# SPI_IFC.net
KiCad netlist of a schematic drawn in Altium Designer
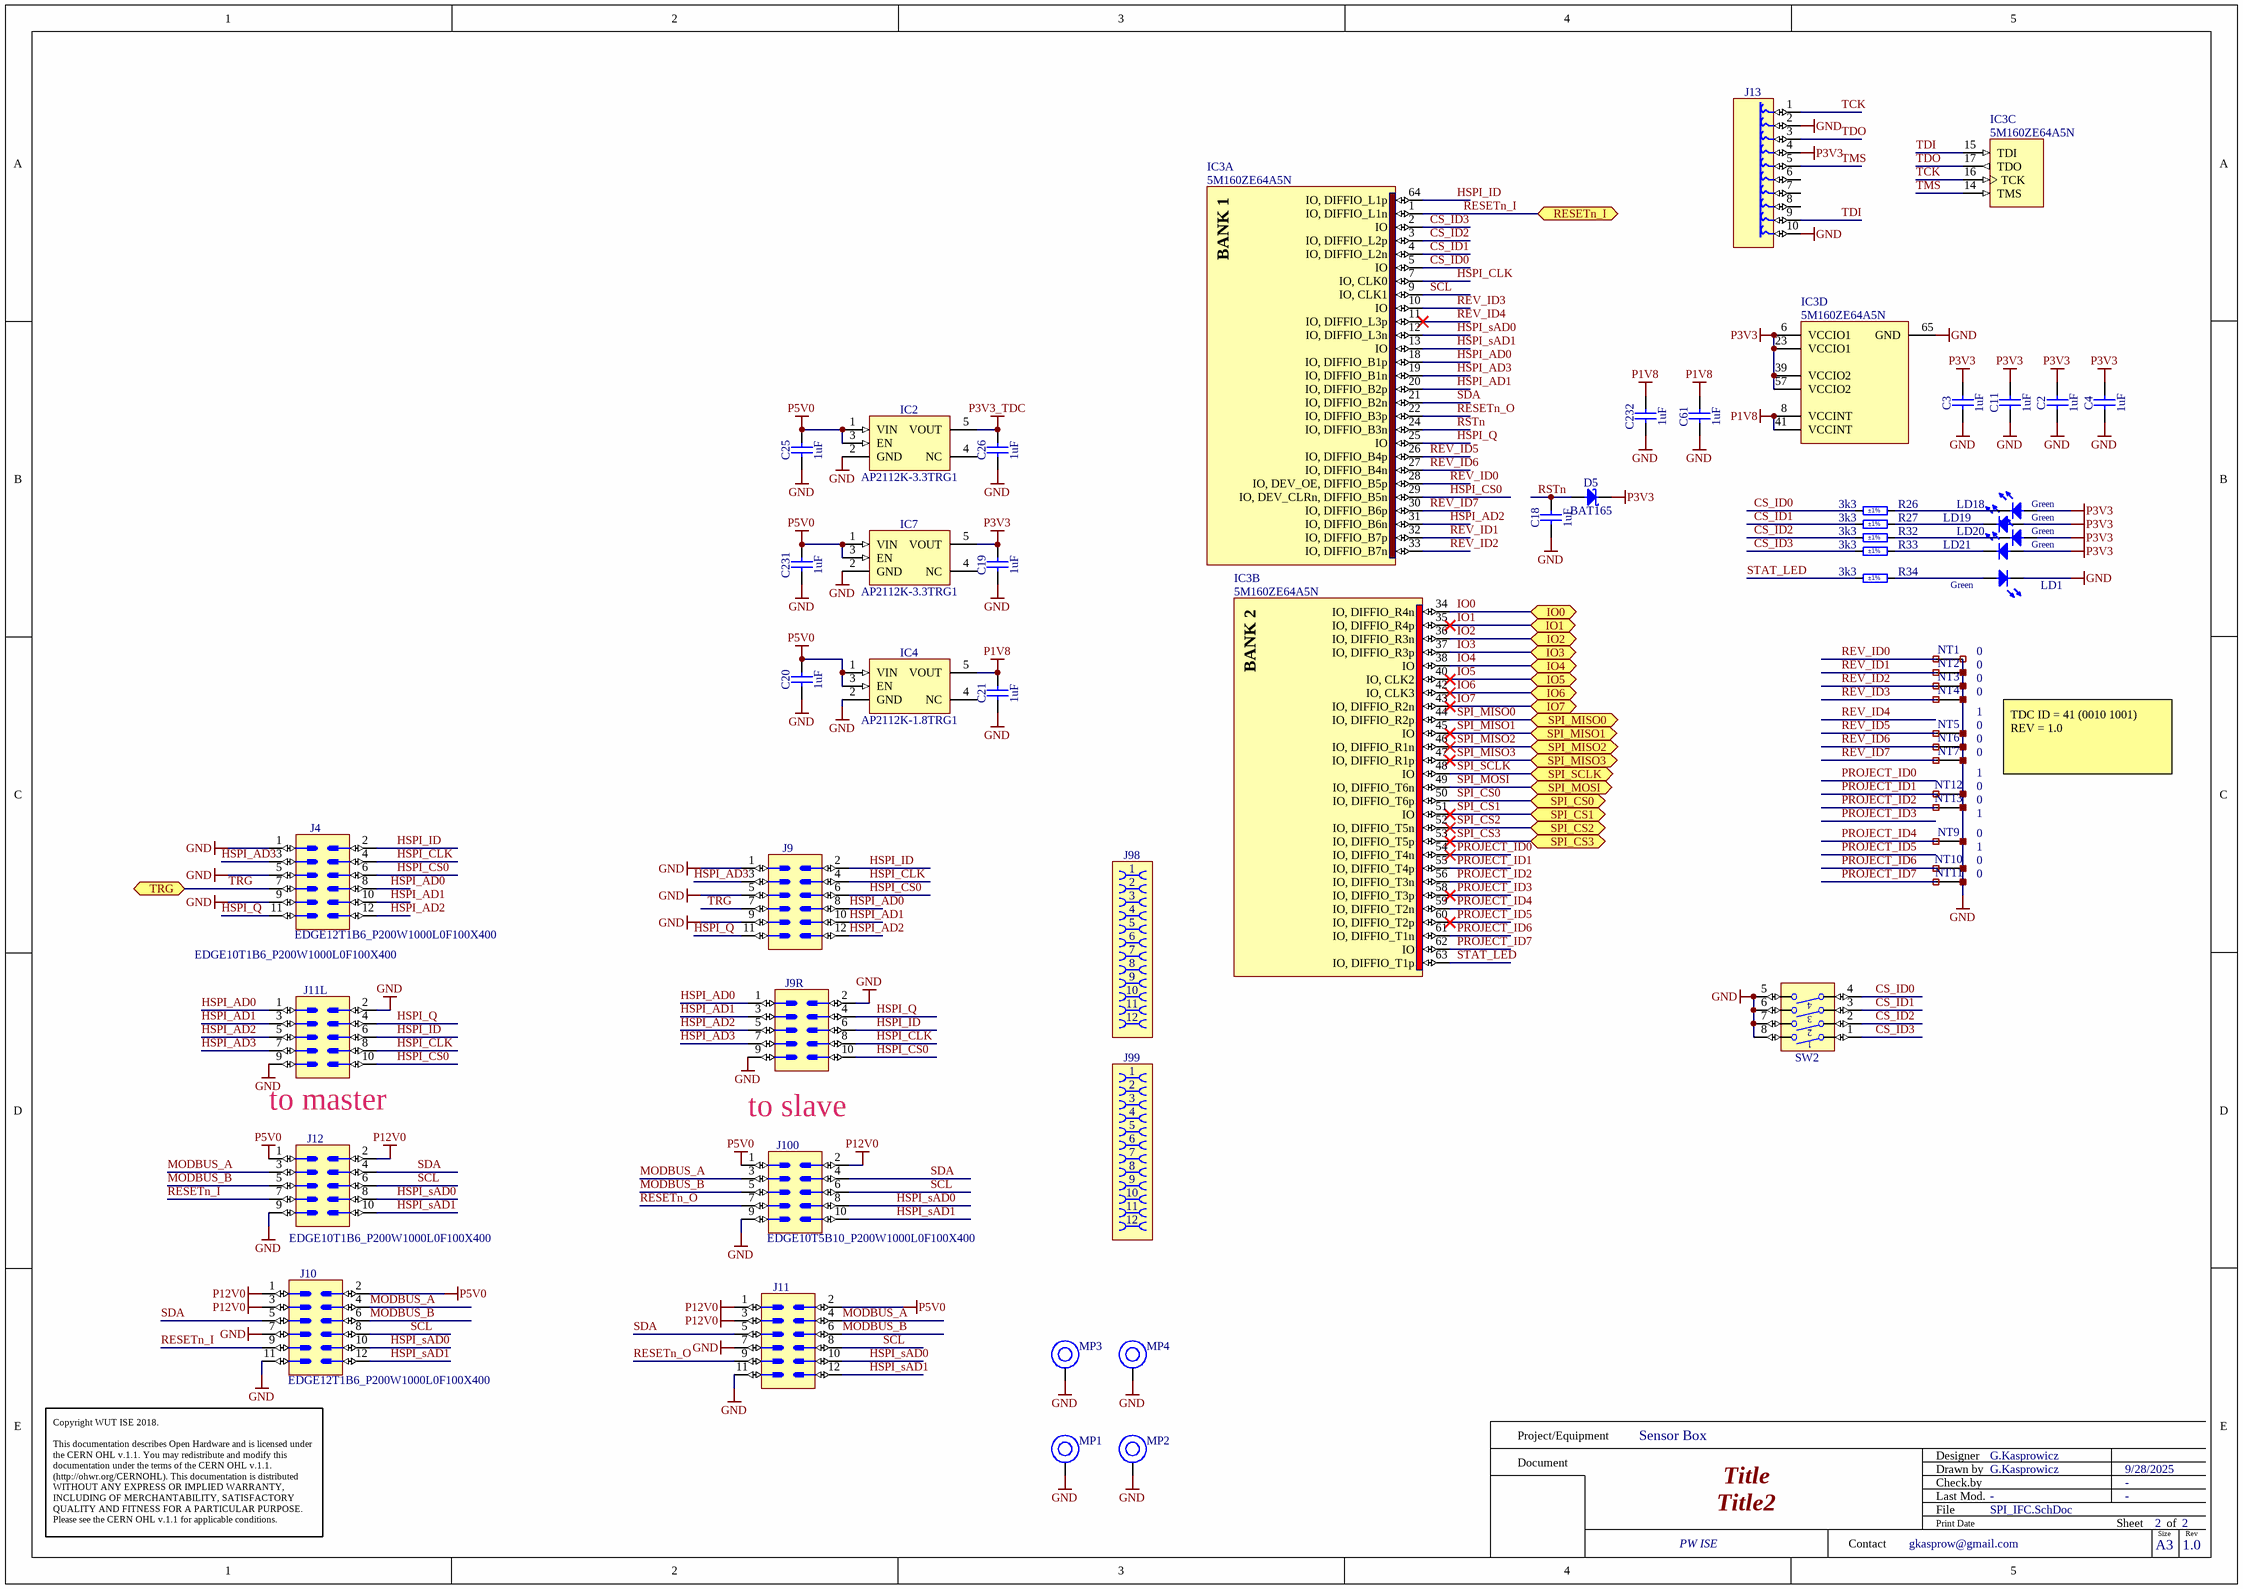
[diagram p0: SPI_IFC.SchDoc]

(export (version "E")
  (design (tool "Eeschema 10.0.6"))
  (components
    (comp (ref "C2")
      (value "1uF")
      (footprint "CAPC1005X55N")
      (description "Non-polarised capacitor")
      (fields
        (field (name "PART NUMBER") "CC0402_1UF_16V_10%_X5R")
        (field (name "VOLTAGE") "16V")
        (field (name "AUTHOR") "CERN DEM JLC")
      )
      (libsource (lib "Capacitors") (part "Capacitor - non polarized"))
    )
    (comp (ref "C3")
      (value "1uF")
      (footprint "CAPC1005X55N")
      (description "Non-polarised capacitor")
      (fields
        (field (name "PART NUMBER") "CC0402_1UF_16V_10%_X5R")
        (field (name "VOLTAGE") "16V")
        (field (name "AUTHOR") "CERN DEM JLC")
      )
      (libsource (lib "Capacitors") (part "Capacitor - non polarized"))
    )
    (comp (ref "C4")
      (value "1uF")
      (footprint "CAPC1005X55N")
      (description "Non-polarised capacitor")
      (fields
        (field (name "PART NUMBER") "CC0402_1UF_16V_10%_X5R")
        (field (name "VOLTAGE") "16V")
        (field (name "AUTHOR") "CERN DEM JLC")
      )
      (libsource (lib "Capacitors") (part "Capacitor - non polarized"))
    )
    (comp (ref "C11")
      (value "1uF")
      (footprint "CAPC1005X55N")
      (description "Non-polarised capacitor")
      (fields
        (field (name "PART NUMBER") "CC0402_1UF_16V_10%_X5R")
        (field (name "VOLTAGE") "16V")
        (field (name "AUTHOR") "CERN DEM JLC")
      )
      (libsource (lib "Capacitors") (part "Capacitor - non polarized"))
    )
    (comp (ref "C18")
      (value "1uF")
      (footprint "CAPC1005X55N")
      (description "Non-polarised capacitor")
      (fields
        (field (name "PART NUMBER") "CC0402_1UF_16V_10%_X5R")
        (field (name "VOLTAGE") "16V")
        (field (name "AUTHOR") "CERN DEM JLC")
      )
      (libsource (lib "Capacitors") (part "Capacitor - non polarized"))
    )
    (comp (ref "C19")
      (value "1uF")
      (footprint "CAPC1005X55N")
      (description "Non-polarised capacitor")
      (fields
        (field (name "PART NUMBER") "CC0402_1UF_16V_10%_X5R")
        (field (name "VOLTAGE") "16V")
        (field (name "AUTHOR") "CERN DEM JLC")
      )
      (libsource (lib "Capacitors") (part "Capacitor - non polarized"))
    )
    (comp (ref "C20")
      (value "1uF")
      (footprint "CAPC1005X55N")
      (description "Non-polarised capacitor")
      (fields
        (field (name "PART NUMBER") "CC0402_1UF_16V_10%_X5R")
        (field (name "VOLTAGE") "16V")
        (field (name "AUTHOR") "CERN DEM JLC")
      )
      (libsource (lib "Capacitors") (part "Capacitor - non polarized"))
    )
    (comp (ref "C21")
      (value "1uF")
      (footprint "CAPC1005X55N")
      (description "Non-polarised capacitor")
      (fields
        (field (name "PART NUMBER") "CC0402_1UF_16V_10%_X5R")
        (field (name "VOLTAGE") "16V")
        (field (name "AUTHOR") "CERN DEM JLC")
      )
      (libsource (lib "Capacitors") (part "Capacitor - non polarized"))
    )
    (comp (ref "C25")
      (value "1uF")
      (footprint "CAPC1005X55N")
      (description "Non-polarised capacitor")
      (fields
        (field (name "PART NUMBER") "CC0402_1UF_16V_10%_X5R")
        (field (name "VOLTAGE") "16V")
        (field (name "AUTHOR") "CERN DEM JLC")
      )
      (libsource (lib "Capacitors") (part "Capacitor - non polarized"))
    )
    (comp (ref "C26")
      (value "1uF")
      (footprint "CAPC1005X55N")
      (description "Non-polarised capacitor")
      (fields
        (field (name "PART NUMBER") "CC0402_1UF_16V_10%_X5R")
        (field (name "VOLTAGE") "16V")
        (field (name "AUTHOR") "CERN DEM JLC")
      )
      (libsource (lib "Capacitors") (part "Capacitor - non polarized"))
    )
    (comp (ref "C61")
      (value "1uF")
      (footprint "CAPC1005X55N")
      (description "Non-polarised capacitor")
      (fields
        (field (name "PART NUMBER") "CC0402_1UF_16V_10%_X5R")
        (field (name "VOLTAGE") "16V")
        (field (name "AUTHOR") "CERN DEM JLC")
      )
      (libsource (lib "Capacitors") (part "Capacitor - non polarized"))
    )
    (comp (ref "C231")
      (value "1uF")
      (footprint "CAPC1005X55N")
      (description "Non-polarised capacitor")
      (fields
        (field (name "PART NUMBER") "CC0402_1UF_16V_10%_X5R")
        (field (name "VOLTAGE") "16V")
        (field (name "AUTHOR") "CERN DEM JLC")
      )
      (libsource (lib "Capacitors") (part "Capacitor - non polarized"))
    )
    (comp (ref "C232")
      (value "1uF")
      (footprint "CAPC1005X55N")
      (description "Non-polarised capacitor")
      (fields
        (field (name "PART NUMBER") "CC0402_1UF_16V_10%_X5R")
        (field (name "VOLTAGE") "16V")
        (field (name "AUTHOR") "CERN DEM JLC")
      )
      (libsource (lib "Capacitors") (part "Capacitor - non polarized"))
    )
    (comp (ref "D5")
      (value "BAT165")
      (footprint "SOD2512X110N")
      (description "Schottky Diode")
      (fields
        (field (name "VOLTAGE") "40V")
        (field (name "POWER") "750mA")
        (field (name "AUTHOR") "CERN DEM JLC")
      )
      (libsource (lib "ICs And Semiconductors") (part "Diode Schottky"))
    )
    (comp (ref "IC2")
      (value "AP2112K-3.3TRG1")
      (footprint "SOT95P285X140-5N")
      (description "600mA CMOS Low Dropout Linear Regulator with Enable")
      (fields
        (field (name "MANUFACTURER") "DIODES INCORPORATED")
        (field (name "MANUFACTURER PART NUMBER") "AP2112K-3.3")
        (field (name "AUTHOR") "CERN DEM MR")
      )
      (libsource (lib "ICs And Semiconductors") (part "AP2112K"))
    )
    (comp (ref "IC3")
      (value "5M160ZE64A5N")
      (footprint "QFP40P900X900X120-65N-S550")
      (fields (field (name "MANUFACTURER") "ALTERA") (field (name "AUTHOR") "CERN DEM JLC"))
      (libsource (lib "ICs And Semiconductors") (part "5M160ZE64A5N"))
    )
    (comp (ref "IC4")
      (value "AP2112K-1.8TRG1")
      (footprint "SOT95P285X140-5N")
      (description "600mA CMOS Low Dropout Linear Regulator with Enable")
      (fields
        (field (name "MANUFACTURER") "DIODES INCORPORATED")
        (field (name "MANUFACTURER PART NUMBER") "AP2112K-1.8")
        (field (name "AUTHOR") "CERN DEM JLC")
      )
      (libsource (lib "ICs And Semiconductors") (part "AP2112K"))
    )
    (comp (ref "IC7")
      (value "AP2112K-3.3TRG1")
      (footprint "SOT95P285X140-5N")
      (description "600mA CMOS Low Dropout Linear Regulator with Enable")
      (fields
        (field (name "MANUFACTURER") "DIODES INCORPORATED")
        (field (name "MANUFACTURER PART NUMBER") "AP2112K-3.3")
        (field (name "AUTHOR") "CERN DEM MR")
      )
      (libsource (lib "ICs And Semiconductors") (part "AP2112K"))
    )
    (comp (ref "J4")
      (value "~")
      (footprint "EDGE12T1B6_P200W1000L0F100X400")
      (description "PCB Edge Connector 12 (2x6)")
      (fields
        (field (name "PART NUMBER") "EDGE10T1B6_P200W1000L0F100X400")
        (field (name "AUTHOR") "CERN DEM MR")
      )
      (libsource (lib "Connectors") (part "PCB Edge Connector 12 (2x6)"))
    )
    (comp (ref "J9")
      (value "~")
      (footprint "EDGE12T5B10_P200W1000L0F100X400")
      (description "PCB Edge Connector 12 (2x6)")
      (fields (field (name "PART NUMBER") "EDGE12T5B10_P200W1000L0F100X400") (field (name "AUTHOR") "GK"))
      (libsource (lib "Connectors") (part "PCB Edge Connector 12 (2x6) R"))
    )
    (comp (ref "J9R")
      (value "~")
      (footprint "EDGE10T5B10_P200W1000L0F100X400")
      (description "PCB Edge Connector 10 (2x5)")
      (fields
        (field (name "PART NUMBER") "EDGE10T5B10_P200W1000L0F100X400")
        (field (name "AUTHOR") "CERN DEM MR")
      )
      (libsource (lib "Connectors") (part "PCB Edge Connector 10 (2x5)"))
    )
    (comp (ref "J10")
      (value "~")
      (footprint "EDGE12T1B6_P200W1000L0F100X400")
      (description "PCB Edge Connector 12 (2x6)")
      (fields
        (field (name "PART NUMBER") "EDGE10T1B6_P200W1000L0F100X400")
        (field (name "AUTHOR") "CERN DEM MR")
      )
      (libsource (lib "Connectors") (part "PCB Edge Connector 12 (2x6)"))
    )
    (comp (ref "J11")
      (value "~")
      (footprint "EDGE12T5B10_P200W1000L0F100X400")
      (description "PCB Edge Connector 12 (2x6)")
      (fields (field (name "PART NUMBER") "EDGE12T5B10_P200W1000L0F100X400") (field (name "AUTHOR") "GK"))
      (libsource (lib "Connectors") (part "PCB Edge Connector 12 (2x6) R"))
    )
    (comp (ref "J11L")
      (value "~")
      (footprint "EDGE10T1B6_P200W1000L0F100X400")
      (description "PCB Edge Connector 10 (2x5)")
      (fields
        (field (name "PART NUMBER") "EDGE10T1B6_P200W1000L0F100X400")
        (field (name "AUTHOR") "CERN DEM MR")
      )
      (libsource (lib "Connectors") (part "PCB Edge Connector 10 (2x5)"))
    )
    (comp (ref "J12")
      (value "~")
      (footprint "EDGE10T1B6_P200W1000L0F100X400")
      (description "PCB Edge Connector 10 (2x5)")
      (fields
        (field (name "PART NUMBER") "EDGE10T1B6_P200W1000L0F100X400")
        (field (name "AUTHOR") "CERN DEM MR")
      )
      (libsource (lib "Connectors") (part "PCB Edge Connector 10 (2x5)"))
    )
    (comp (ref "J13")
      (value "TC2050-IDC")
      (footprint "TC2050-IDC")
      (description "TC2030-MCP and TC2050-IDC Pad Contact")
      (fields (field (name "AUTHOR") "CERN DEM HF"))
      (libsource (lib "Eletro-mechanical") (part "TC2050-IDC"))
    )
    (comp (ref "J98")
      (value "~")
      (footprint "AVX_009159012761916")
      (description "Open Ended Card Edge Connector, 9159 Series")
      (fields
        (field (name "PART NUMBER") "AVX_0009159012761916")
        (field (name "MANUFACTURER") "AVX")
        (field (name "AUTHOR") "GK")
      )
      (libsource (lib "Connectors") (part "AVX_009159012761916"))
    )
    (comp (ref "J99")
      (value "~")
      (footprint "AVX_009159012761916")
      (description "Open Ended Card Edge Connector, 9159 Series")
      (fields
        (field (name "PART NUMBER") "AVX_0009159012761916")
        (field (name "MANUFACTURER") "AVX")
        (field (name "AUTHOR") "GK")
      )
      (libsource (lib "Connectors") (part "AVX_009159012761916"))
    )
    (comp (ref "J100")
      (value "~")
      (footprint "EDGE10T5B10_P200W1000L0F100X400")
      (description "PCB Edge Connector 10 (2x5)")
      (fields
        (field (name "PART NUMBER") "EDGE10T5B10_P200W1000L0F100X400")
        (field (name "AUTHOR") "CERN DEM MR")
      )
      (libsource (lib "Connectors") (part "PCB Edge Connector 10 (2x5)"))
    )
    (comp (ref "LD1")
      (value "Green")
      (footprint "LED_KINGBRIGHT_KP-1608CGCK")
      (description "LED Green 1C 2A")
      (fields
        (field (name "PART NUMBER") "LED_KINGBRIGHT_KP-1608CGCK")
        (field (name "MANUFACTURER") "KINGBRIGHT")
        (field (name "AUTHOR") "CERN DEM HF")
      )
      (libsource (lib "ICs And Semiconductors") (part "LED Green 1C 2A"))
    )
    (comp (ref "LD18")
      (value "Green")
      (footprint "LED_KINGBRIGHT_KP-1608CGCK")
      (description "LED Green 1C 2A")
      (fields
        (field (name "PART NUMBER") "LED_KINGBRIGHT_KP-1608CGCK")
        (field (name "MANUFACTURER") "KINGBRIGHT")
        (field (name "AUTHOR") "CERN DEM HF")
      )
      (libsource (lib "ICs And Semiconductors") (part "LED Green 1C 2A"))
    )
    (comp (ref "LD19")
      (value "Green")
      (footprint "LED_KINGBRIGHT_KP-1608CGCK")
      (description "LED Green 1C 2A")
      (fields
        (field (name "PART NUMBER") "LED_KINGBRIGHT_KP-1608CGCK")
        (field (name "MANUFACTURER") "KINGBRIGHT")
        (field (name "AUTHOR") "CERN DEM HF")
      )
      (libsource (lib "ICs And Semiconductors") (part "LED Green 1C 2A"))
    )
    (comp (ref "LD20")
      (value "Green")
      (footprint "LED_KINGBRIGHT_KP-1608CGCK")
      (description "LED Green 1C 2A")
      (fields
        (field (name "PART NUMBER") "LED_KINGBRIGHT_KP-1608CGCK")
        (field (name "MANUFACTURER") "KINGBRIGHT")
        (field (name "AUTHOR") "CERN DEM HF")
      )
      (libsource (lib "ICs And Semiconductors") (part "LED Green 1C 2A"))
    )
    (comp (ref "LD21")
      (value "Green")
      (footprint "LED_KINGBRIGHT_KP-1608CGCK")
      (description "LED Green 1C 2A")
      (fields
        (field (name "PART NUMBER") "LED_KINGBRIGHT_KP-1608CGCK")
        (field (name "MANUFACTURER") "KINGBRIGHT")
        (field (name "AUTHOR") "CERN DEM HF")
      )
      (libsource (lib "ICs And Semiconductors") (part "LED Green 1C 2A"))
    )
    (comp (ref "MP1")
      (value "M1.6 x 3mm")
      (footprint "97730306330")
      (description "WA-SMSI SMT Steel Spacer with internal Thread Bottom closed, OD 3.3mm, M1.6 x 3mm")
      (fields
        (field (name "MANUFACTURER PART NUMBER") "97730306330R")
        (field (name "MANUFACTURER") "Wurth Elektronik")
      )
      (libsource (lib "Altium_WA-SMSI (rev22a)") (part "97730306330R"))
    )
    (comp (ref "MP2")
      (value "M1.6 x 3mm")
      (footprint "97730306330")
      (description "WA-SMSI SMT Steel Spacer with internal Thread Bottom closed, OD 3.3mm, M1.6 x 3mm")
      (fields
        (field (name "MANUFACTURER PART NUMBER") "97730306330R")
        (field (name "MANUFACTURER") "Wurth Elektronik")
      )
      (libsource (lib "Altium_WA-SMSI (rev22a)") (part "97730306330R"))
    )
    (comp (ref "MP3")
      (value "M1.6 x 3mm")
      (footprint "97730306330")
      (description "WA-SMSI SMT Steel Spacer with internal Thread Bottom closed, OD 3.3mm, M1.6 x 3mm")
      (fields
        (field (name "MANUFACTURER PART NUMBER") "97730306330R")
        (field (name "MANUFACTURER") "Wurth Elektronik")
      )
      (libsource (lib "Altium_WA-SMSI (rev22a)") (part "97730306330R"))
    )
    (comp (ref "MP4")
      (value "M1.6 x 3mm")
      (footprint "97730306330")
      (description "WA-SMSI SMT Steel Spacer with internal Thread Bottom closed, OD 3.3mm, M1.6 x 3mm")
      (fields
        (field (name "MANUFACTURER PART NUMBER") "97730306330R")
        (field (name "MANUFACTURER") "Wurth Elektronik")
      )
      (libsource (lib "Altium_WA-SMSI (rev22a)") (part "97730306330R"))
    )
    (comp (ref "NT1")
      (value "Net Tie")
      (footprint "Net Tie 3")
      (fields (field (name "PART NUMBER") "Net Tie 3") (field (name "AUTHOR") "CERN DEM HF"))
      (libsource (lib "Eletro-mechanical") (part "Net Tie_a"))
    )
    (comp (ref "NT2")
      (value "Net Tie")
      (footprint "Net Tie 3")
      (fields (field (name "PART NUMBER") "Net Tie 3") (field (name "AUTHOR") "CERN DEM HF"))
      (libsource (lib "Eletro-mechanical") (part "Net Tie_a"))
    )
    (comp (ref "NT3")
      (value "Net Tie")
      (footprint "Net Tie 3")
      (fields (field (name "PART NUMBER") "Net Tie 3") (field (name "AUTHOR") "CERN DEM HF"))
      (libsource (lib "Eletro-mechanical") (part "Net Tie_a"))
    )
    (comp (ref "NT4")
      (value "Net Tie")
      (footprint "Net Tie 3")
      (fields (field (name "PART NUMBER") "Net Tie 3") (field (name "AUTHOR") "CERN DEM HF"))
      (libsource (lib "Eletro-mechanical") (part "Net Tie_a"))
    )
    (comp (ref "NT5")
      (value "Net Tie")
      (footprint "Net Tie 3")
      (fields (field (name "PART NUMBER") "Net Tie 3") (field (name "AUTHOR") "CERN DEM HF"))
      (libsource (lib "Eletro-mechanical") (part "Net Tie_a"))
    )
    (comp (ref "NT6")
      (value "Net Tie")
      (footprint "Net Tie 3")
      (fields (field (name "PART NUMBER") "Net Tie 3") (field (name "AUTHOR") "CERN DEM HF"))
      (libsource (lib "Eletro-mechanical") (part "Net Tie_a"))
    )
    (comp (ref "NT7")
      (value "Net Tie")
      (footprint "Net Tie 3")
      (fields (field (name "PART NUMBER") "Net Tie 3") (field (name "AUTHOR") "CERN DEM HF"))
      (libsource (lib "Eletro-mechanical") (part "Net Tie_a"))
    )
    (comp (ref "NT9")
      (value "Net Tie")
      (footprint "Net Tie 3")
      (fields (field (name "PART NUMBER") "Net Tie 3") (field (name "AUTHOR") "CERN DEM HF"))
      (libsource (lib "Eletro-mechanical") (part "Net Tie_a"))
    )
    (comp (ref "NT10")
      (value "Net Tie")
      (footprint "Net Tie 3")
      (fields (field (name "PART NUMBER") "Net Tie 3") (field (name "AUTHOR") "CERN DEM HF"))
      (libsource (lib "Eletro-mechanical") (part "Net Tie_a"))
    )
    (comp (ref "NT11")
      (value "Net Tie")
      (footprint "Net Tie 3")
      (fields (field (name "PART NUMBER") "Net Tie 3") (field (name "AUTHOR") "CERN DEM HF"))
      (libsource (lib "Eletro-mechanical") (part "Net Tie_a"))
    )
    (comp (ref "NT12")
      (value "Net Tie")
      (footprint "Net Tie 3")
      (fields (field (name "PART NUMBER") "Net Tie 3") (field (name "AUTHOR") "CERN DEM HF"))
      (libsource (lib "Eletro-mechanical") (part "Net Tie_a"))
    )
    (comp (ref "NT13")
      (value "Net Tie")
      (footprint "Net Tie 3")
      (fields (field (name "PART NUMBER") "Net Tie 3") (field (name "AUTHOR") "CERN DEM HF"))
      (libsource (lib "Eletro-mechanical") (part "Net Tie_a"))
    )
    (comp (ref "R26")
      (value "3k3")
      (footprint "RESC1005X40N")
      (description "Resistor - 1%")
      (fields
        (field (name "TOLERANCE") "±1%")
        (field (name "PART NUMBER") "R0402_3K3_1%_0.0625W_100PPM")
        (field (name "POWER") "0.0625W")
        (field (name "AUTHOR") "CERN DEM JLC")
      )
      (libsource (lib "Resistors") (part "Resistor - 1%"))
    )
    (comp (ref "R27")
      (value "3k3")
      (footprint "RESC1005X40N")
      (description "Resistor - 1%")
      (fields
        (field (name "TOLERANCE") "±1%")
        (field (name "PART NUMBER") "R0402_3K3_1%_0.0625W_100PPM")
        (field (name "POWER") "0.0625W")
        (field (name "AUTHOR") "CERN DEM JLC")
      )
      (libsource (lib "Resistors") (part "Resistor - 1%"))
    )
    (comp (ref "R32")
      (value "3k3")
      (footprint "RESC1005X40N")
      (description "Resistor - 1%")
      (fields
        (field (name "TOLERANCE") "±1%")
        (field (name "PART NUMBER") "R0402_3K3_1%_0.0625W_100PPM")
        (field (name "POWER") "0.0625W")
        (field (name "AUTHOR") "CERN DEM JLC")
      )
      (libsource (lib "Resistors") (part "Resistor - 1%"))
    )
    (comp (ref "R33")
      (value "3k3")
      (footprint "RESC1005X40N")
      (description "Resistor - 1%")
      (fields
        (field (name "TOLERANCE") "±1%")
        (field (name "PART NUMBER") "R0402_3K3_1%_0.0625W_100PPM")
        (field (name "POWER") "0.0625W")
        (field (name "AUTHOR") "CERN DEM JLC")
      )
      (libsource (lib "Resistors") (part "Resistor - 1%"))
    )
    (comp (ref "R34")
      (value "3k3")
      (footprint "RESC1005X40N")
      (description "Resistor - 1%")
      (fields
        (field (name "TOLERANCE") "±1%")
        (field (name "PART NUMBER") "R0402_3K3_1%_0.0625W_100PPM")
        (field (name "POWER") "0.0625W")
        (field (name "AUTHOR") "CERN DEM JLC")
      )
      (libsource (lib "Resistors") (part "Resistor - 1%"))
    )
    (comp (ref "SW2")
      (value "Switch")
      (footprint "SW_OMRON_A6H-4102")
      (description "4 Ways SPST DIP Switch")
      (fields
        (field (name "PART NUMBER") "SW_OMRON_A6H-4102")
        (field (name "MANUFACTURER") "OMRON")
        (field (name "AUTHOR") "CERN DEM JLC")
      )
      (libsource (lib "Eletro-mechanical") (part "SW 4x SPST DIP Switch"))
    )
  )
  (nets
    (net (code "1") (name "/CS_ID0") (class "Default")
      (node (ref "IC3") (pin "5") (pinfunction "IO_5") (pintype "bidirectional"))
      (node (ref "R26") (pin "2") (pinfunction "2_2") (pintype "passive"))
      (node (ref "SW2") (pin "4") (pinfunction "4_4") (pintype "bidirectional"))
    )
    (net (code "2") (name "/CS_ID1") (class "Default")
      (node (ref "IC3") (pin "4") (pinfunction "IO,_DIFFIO_L2n_4") (pintype "bidirectional"))
      (node (ref "R27") (pin "2") (pinfunction "2_2") (pintype "passive"))
      (node (ref "SW2") (pin "3") (pinfunction "3_3") (pintype "bidirectional"))
    )
    (net (code "3") (name "/CS_ID2") (class "Default")
      (node (ref "IC3") (pin "3") (pinfunction "IO,_DIFFIO_L2p_3") (pintype "bidirectional"))
      (node (ref "R32") (pin "2") (pinfunction "2_2") (pintype "passive"))
      (node (ref "SW2") (pin "2") (pinfunction "2_2") (pintype "bidirectional"))
    )
    (net (code "4") (name "/CS_ID3") (class "Default")
      (node (ref "IC3") (pin "2") (pinfunction "IO_2") (pintype "bidirectional"))
      (node (ref "R33") (pin "2") (pinfunction "2_2") (pintype "passive"))
      (node (ref "SW2") (pin "1") (pinfunction "1_1") (pintype "bidirectional"))
    )
    (net (code "5") (name "/HSPI_AD0") (class "Default")
      (node (ref "IC3") (pin "18") (pinfunction "IO,_DIFFIO_B1p_18") (pintype "bidirectional"))
      (node (ref "J11L") (pin "1") (pinfunction "1_1") (pintype "bidirectional"))
      (node (ref "J4") (pin "8") (pinfunction "8_8") (pintype "bidirectional"))
      (node (ref "J9") (pin "8") (pinfunction "8_8") (pintype "bidirectional"))
      (node (ref "J9R") (pin "1") (pinfunction "1_1") (pintype "bidirectional"))
    )
    (net (code "6") (name "/HSPI_AD1") (class "Default")
      (node (ref "IC3") (pin "20") (pinfunction "IO,_DIFFIO_B2p_20") (pintype "bidirectional"))
      (node (ref "J11L") (pin "3") (pinfunction "3_3") (pintype "bidirectional"))
      (node (ref "J4") (pin "10") (pinfunction "10_10") (pintype "bidirectional"))
      (node (ref "J9") (pin "10") (pinfunction "10_10") (pintype "bidirectional"))
      (node (ref "J9R") (pin "3") (pinfunction "3_3") (pintype "bidirectional"))
    )
    (net (code "7") (name "/HSPI_AD2") (class "Default")
      (node (ref "IC3") (pin "31") (pinfunction "IO,_DIFFIO_B6n_31") (pintype "bidirectional"))
      (node (ref "J11L") (pin "5") (pinfunction "5_5") (pintype "bidirectional"))
      (node (ref "J4") (pin "12") (pinfunction "12_12") (pintype "bidirectional"))
      (node (ref "J9") (pin "12") (pinfunction "12_12") (pintype "bidirectional"))
      (node (ref "J9R") (pin "5") (pinfunction "5_5") (pintype "bidirectional"))
    )
    (net (code "8") (name "/HSPI_AD3") (class "Default")
      (node (ref "IC3") (pin "19") (pinfunction "IO,_DIFFIO_B1n_19") (pintype "bidirectional"))
      (node (ref "J11L") (pin "7") (pinfunction "7_7") (pintype "bidirectional"))
      (node (ref "J4") (pin "3") (pinfunction "3_3") (pintype "bidirectional"))
      (node (ref "J9") (pin "3") (pinfunction "3_3") (pintype "bidirectional"))
      (node (ref "J9R") (pin "7") (pinfunction "7_7") (pintype "bidirectional"))
    )
    (net (code "9") (name "/HSPI_CLK") (class "Default")
      (node (ref "IC3") (pin "7") (pinfunction "IO,_CLK0_7") (pintype "bidirectional"))
      (node (ref "J11L") (pin "8") (pinfunction "8_8") (pintype "bidirectional"))
      (node (ref "J4") (pin "4") (pinfunction "4_4") (pintype "bidirectional"))
      (node (ref "J9") (pin "4") (pinfunction "4_4") (pintype "bidirectional"))
      (node (ref "J9R") (pin "8") (pinfunction "8_8") (pintype "bidirectional"))
    )
    (net (code "10") (name "/HSPI_CS0") (class "Default")
      (node (ref "IC3") (pin "29") (pinfunction "IO,_DEV_CLRn,_DIFFIO_B5n_29") (pintype "bidirectional"))
      (node (ref "J11L") (pin "10") (pinfunction "10_10") (pintype "bidirectional"))
      (node (ref "J4") (pin "6") (pinfunction "6_6") (pintype "bidirectional"))
      (node (ref "J9") (pin "6") (pinfunction "6_6") (pintype "bidirectional"))
      (node (ref "J9R") (pin "10") (pinfunction "10_10") (pintype "bidirectional"))
    )
    (net (code "11") (name "/HSPI_ID") (class "Default")
      (node (ref "IC3") (pin "64") (pinfunction "IO,_DIFFIO_L1p_64") (pintype "bidirectional"))
      (node (ref "J11L") (pin "6") (pinfunction "6_6") (pintype "bidirectional"))
      (node (ref "J4") (pin "2") (pinfunction "2_2") (pintype "bidirectional"))
      (node (ref "J9") (pin "2") (pinfunction "2_2") (pintype "bidirectional"))
      (node (ref "J9R") (pin "6") (pinfunction "6_6") (pintype "bidirectional"))
    )
    (net (code "12") (name "/HSPI_Q") (class "Default")
      (node (ref "IC3") (pin "25") (pinfunction "IO_25") (pintype "bidirectional"))
      (node (ref "J11L") (pin "4") (pinfunction "4_4") (pintype "bidirectional"))
      (node (ref "J4") (pin "11") (pinfunction "11_11") (pintype "bidirectional"))
      (node (ref "J9") (pin "11") (pinfunction "11_11") (pintype "bidirectional"))
      (node (ref "J9R") (pin "4") (pinfunction "4_4") (pintype "bidirectional"))
    )
    (net (code "13") (name "/HSPI_sAD0") (class "Default")
      (node (ref "IC3") (pin "12") (pinfunction "IO,_DIFFIO_L3n_12") (pintype "bidirectional"))
      (node (ref "J10") (pin "10") (pinfunction "10_10") (pintype "bidirectional"))
      (node (ref "J100") (pin "8") (pinfunction "8_8") (pintype "bidirectional"))
      (node (ref "J11") (pin "10") (pinfunction "10_10") (pintype "bidirectional"))
      (node (ref "J12") (pin "8") (pinfunction "8_8") (pintype "bidirectional"))
    )
    (net (code "14") (name "/HSPI_sAD1") (class "Default")
      (node (ref "IC3") (pin "13") (pinfunction "IO_13") (pintype "bidirectional"))
      (node (ref "J10") (pin "12") (pinfunction "12_12") (pintype "bidirectional"))
      (node (ref "J100") (pin "10") (pinfunction "10_10") (pintype "bidirectional"))
      (node (ref "J11") (pin "12") (pinfunction "12_12") (pintype "bidirectional"))
      (node (ref "J12") (pin "10") (pinfunction "10_10") (pintype "bidirectional"))
    )
    (net (code "15") (name "/IO0") (class "Default")
      (node (ref "IC3") (pin "34") (pinfunction "IO,_DIFFIO_R4n_34") (pintype "bidirectional"))
    )
    (net (code "16") (name "/IO1") (class "Default")
      (node (ref "IC3") (pin "35") (pinfunction "IO,_DIFFIO_R4p_35") (pintype "bidirectional+no_connect"))
    )
    (net (code "17") (name "/IO2") (class "Default")
      (node (ref "IC3") (pin "36") (pinfunction "IO,_DIFFIO_R3n_36") (pintype "bidirectional"))
    )
    (net (code "18") (name "/IO3") (class "Default")
      (node (ref "IC3") (pin "37") (pinfunction "IO,_DIFFIO_R3p_37") (pintype "bidirectional"))
    )
    (net (code "19") (name "/IO4") (class "Default")
      (node (ref "IC3") (pin "38") (pinfunction "IO_38") (pintype "bidirectional"))
    )
    (net (code "20") (name "/IO5") (class "Default")
      (node (ref "IC3") (pin "40") (pinfunction "IO,_CLK2_40") (pintype "bidirectional+no_connect"))
    )
    (net (code "21") (name "/IO6") (class "Default")
      (node (ref "IC3") (pin "42") (pinfunction "IO,_CLK3_42") (pintype "bidirectional+no_connect"))
    )
    (net (code "22") (name "/IO7") (class "Default")
      (node (ref "IC3") (pin "43") (pinfunction "IO,_DIFFIO_R2n_43") (pintype "bidirectional+no_connect"))
    )
    (net (code "23") (name "/MODBUS_A") (class "Default")
      (node (ref "J10") (pin "4") (pinfunction "4_4") (pintype "bidirectional"))
      (node (ref "J100") (pin "3") (pinfunction "3_3") (pintype "bidirectional"))
      (node (ref "J11") (pin "4") (pinfunction "4_4") (pintype "bidirectional"))
      (node (ref "J12") (pin "3") (pinfunction "3_3") (pintype "bidirectional"))
    )
    (net (code "24") (name "/MODBUS_B") (class "Default")
      (node (ref "J10") (pin "6") (pinfunction "6_6") (pintype "bidirectional"))
      (node (ref "J100") (pin "5") (pinfunction "5_5") (pintype "bidirectional"))
      (node (ref "J11") (pin "6") (pinfunction "6_6") (pintype "bidirectional"))
      (node (ref "J12") (pin "5") (pinfunction "5_5") (pintype "bidirectional"))
    )
    (net (code "25") (name "/PROJECT_ID0") (class "Default")
      (node (ref "IC3") (pin "54") (pinfunction "IO,_DIFFIO_T4n_54") (pintype "bidirectional+no_connect"))
    )
    (net (code "26") (name "/PROJECT_ID1") (class "Default")
      (node (ref "IC3") (pin "55") (pinfunction "IO,_DIFFIO_T4p_55") (pintype "bidirectional"))
      (node (ref "NT12") (pin "1") (pinfunction "1_1") (pintype "bidirectional"))
    )
    (net (code "27") (name "/PROJECT_ID2") (class "Default")
      (node (ref "IC3") (pin "56") (pinfunction "IO,_DIFFIO_T3n_56") (pintype "bidirectional"))
      (node (ref "NT13") (pin "1") (pinfunction "1_1") (pintype "bidirectional"))
    )
    (net (code "28") (name "/PROJECT_ID3") (class "Default")
      (node (ref "IC3") (pin "58") (pinfunction "IO,_DIFFIO_T3p_58") (pintype "bidirectional+no_connect"))
    )
    (net (code "29") (name "/PROJECT_ID4") (class "Default")
      (node (ref "IC3") (pin "59") (pinfunction "IO,_DIFFIO_T2n_59") (pintype "bidirectional"))
      (node (ref "NT9") (pin "1") (pinfunction "1_1") (pintype "bidirectional"))
    )
    (net (code "30") (name "/PROJECT_ID5") (class "Default")
      (node (ref "IC3") (pin "60") (pinfunction "IO,_DIFFIO_T2p_60") (pintype "bidirectional+no_connect"))
    )
    (net (code "31") (name "/PROJECT_ID6") (class "Default")
      (node (ref "IC3") (pin "61") (pinfunction "IO,_DIFFIO_T1n_61") (pintype "bidirectional"))
      (node (ref "NT10") (pin "1") (pinfunction "1_1") (pintype "bidirectional"))
    )
    (net (code "32") (name "/PROJECT_ID7") (class "Default")
      (node (ref "IC3") (pin "62") (pinfunction "IO_62") (pintype "bidirectional"))
      (node (ref "NT11") (pin "1") (pinfunction "1_1") (pintype "bidirectional"))
    )
    (net (code "33") (name "/RESETn_I") (class "Default")
      (node (ref "IC3") (pin "1") (pinfunction "IO,_DIFFIO_L1n_1") (pintype "bidirectional"))
      (node (ref "J10") (pin "9") (pinfunction "9_9") (pintype "bidirectional"))
      (node (ref "J12") (pin "7") (pinfunction "7_7") (pintype "bidirectional"))
    )
    (net (code "34") (name "/RESETn_O") (class "Default")
      (node (ref "IC3") (pin "22") (pinfunction "IO,_DIFFIO_B3p_22") (pintype "bidirectional"))
      (node (ref "J100") (pin "7") (pinfunction "7_7") (pintype "bidirectional"))
      (node (ref "J11") (pin "9") (pinfunction "9_9") (pintype "bidirectional"))
    )
    (net (code "35") (name "/REV_ID0") (class "Default")
      (node (ref "IC3") (pin "28") (pinfunction "IO,_DEV_OE,_DIFFIO_B5p_28") (pintype "bidirectional"))
      (node (ref "NT1") (pin "1") (pinfunction "1_1") (pintype "bidirectional"))
    )
    (net (code "36") (name "/REV_ID1") (class "Default")
      (node (ref "IC3") (pin "32") (pinfunction "IO,_DIFFIO_B7p_32") (pintype "bidirectional"))
      (node (ref "NT2") (pin "1") (pinfunction "1_1") (pintype "bidirectional"))
    )
    (net (code "37") (name "/REV_ID2") (class "Default")
      (node (ref "IC3") (pin "33") (pinfunction "IO,_DIFFIO_B7n_33") (pintype "bidirectional"))
      (node (ref "NT3") (pin "1") (pinfunction "1_1") (pintype "bidirectional"))
    )
    (net (code "38") (name "/REV_ID3") (class "Default")
      (node (ref "IC3") (pin "10") (pinfunction "IO_10") (pintype "bidirectional"))
      (node (ref "NT4") (pin "1") (pinfunction "1_1") (pintype "bidirectional"))
    )
    (net (code "39") (name "/REV_ID4") (class "Default")
      (node (ref "IC3") (pin "11") (pinfunction "IO,_DIFFIO_L3p_11") (pintype "bidirectional"))
    )
    (net (code "40") (name "/REV_ID5") (class "Default")
      (node (ref "IC3") (pin "26") (pinfunction "IO,_DIFFIO_B4p_26") (pintype "bidirectional"))
      (node (ref "NT5") (pin "1") (pinfunction "1_1") (pintype "bidirectional"))
    )
    (net (code "41") (name "/REV_ID6") (class "Default")
      (node (ref "IC3") (pin "27") (pinfunction "IO,_DIFFIO_B4n_27") (pintype "bidirectional"))
      (node (ref "NT6") (pin "1") (pinfunction "1_1") (pintype "bidirectional"))
    )
    (net (code "42") (name "/REV_ID7") (class "Default")
      (node (ref "IC3") (pin "30") (pinfunction "IO,_DIFFIO_B6p_30") (pintype "bidirectional"))
      (node (ref "NT7") (pin "1") (pinfunction "1_1") (pintype "bidirectional"))
    )
    (net (code "43") (name "/RSTn") (class "Default")
      (node (ref "C18") (pin "2") (pinfunction "2_2") (pintype "passive"))
      (node (ref "D5") (pin "2") (pinfunction "A_2") (pintype "passive"))
      (node (ref "IC3") (pin "24") (pinfunction "IO,_DIFFIO_B3n_24") (pintype "bidirectional"))
    )
    (net (code "44") (name "/SCL") (class "Default")
      (node (ref "IC3") (pin "9") (pinfunction "IO,_CLK1_9") (pintype "bidirectional"))
      (node (ref "J10") (pin "8") (pinfunction "8_8") (pintype "bidirectional"))
      (node (ref "J100") (pin "6") (pinfunction "6_6") (pintype "bidirectional"))
      (node (ref "J11") (pin "8") (pinfunction "8_8") (pintype "bidirectional"))
      (node (ref "J12") (pin "6") (pinfunction "6_6") (pintype "bidirectional"))
    )
    (net (code "45") (name "/SDA") (class "Default")
      (node (ref "IC3") (pin "21") (pinfunction "IO,_DIFFIO_B2n_21") (pintype "bidirectional"))
      (node (ref "J10") (pin "5") (pinfunction "5_5") (pintype "bidirectional"))
      (node (ref "J100") (pin "4") (pinfunction "4_4") (pintype "bidirectional"))
      (node (ref "J11") (pin "5") (pinfunction "5_5") (pintype "bidirectional"))
      (node (ref "J12") (pin "4") (pinfunction "4_4") (pintype "bidirectional"))
    )
    (net (code "46") (name "/SPI_CS0") (class "Default")
      (node (ref "IC3") (pin "50") (pinfunction "IO,_DIFFIO_T6p_50") (pintype "bidirectional"))
    )
    (net (code "47") (name "/SPI_CS1") (class "Default")
      (node (ref "IC3") (pin "51") (pinfunction "IO_51") (pintype "bidirectional+no_connect"))
    )
    (net (code "48") (name "/SPI_CS2") (class "Default")
      (node (ref "IC3") (pin "52") (pinfunction "IO,_DIFFIO_T5n_52") (pintype "bidirectional+no_connect"))
    )
    (net (code "49") (name "/SPI_CS3") (class "Default")
      (node (ref "IC3") (pin "53") (pinfunction "IO,_DIFFIO_T5p_53") (pintype "bidirectional+no_connect"))
    )
    (net (code "50") (name "/SPI_MISO0") (class "Default")
      (node (ref "IC3") (pin "44") (pinfunction "IO,_DIFFIO_R2p_44") (pintype "bidirectional"))
    )
    (net (code "51") (name "/SPI_MISO1") (class "Default")
      (node (ref "IC3") (pin "45") (pinfunction "IO_45") (pintype "bidirectional+no_connect"))
    )
    (net (code "52") (name "/SPI_MISO2") (class "Default")
      (node (ref "IC3") (pin "46") (pinfunction "IO,_DIFFIO_R1n_46") (pintype "bidirectional+no_connect"))
    )
    (net (code "53") (name "/SPI_MISO3") (class "Default")
      (node (ref "IC3") (pin "47") (pinfunction "IO,_DIFFIO_R1p_47") (pintype "bidirectional+no_connect"))
    )
    (net (code "54") (name "/SPI_MOSI") (class "Default")
      (node (ref "IC3") (pin "49") (pinfunction "IO,_DIFFIO_T6n_49") (pintype "bidirectional"))
    )
    (net (code "55") (name "/SPI_SCLK") (class "Default")
      (node (ref "IC3") (pin "48") (pinfunction "IO_48") (pintype "bidirectional"))
    )
    (net (code "56") (name "/STAT_LED") (class "Default")
      (node (ref "IC3") (pin "63") (pinfunction "IO,_DIFFIO_T1p_63") (pintype "bidirectional"))
      (node (ref "R34") (pin "2") (pinfunction "2_2") (pintype "passive"))
    )
    (net (code "57") (name "/TCK") (class "Default")
      (node (ref "IC3") (pin "16") (pinfunction "TCK_16") (pintype "input"))
      (node (ref "J13") (pin "1") (pinfunction "1_1") (pintype "bidirectional"))
    )
    (net (code "58") (name "/TDI") (class "Default")
      (node (ref "IC3") (pin "15") (pinfunction "TDI_15") (pintype "input"))
      (node (ref "J13") (pin "9") (pinfunction "9_9") (pintype "bidirectional"))
    )
    (net (code "59") (name "/TDO") (class "Default")
      (node (ref "IC3") (pin "17") (pinfunction "TDO_17") (pintype "output"))
      (node (ref "J13") (pin "3") (pinfunction "3_3") (pintype "bidirectional"))
    )
    (net (code "60") (name "/TMS") (class "Default")
      (node (ref "IC3") (pin "14") (pinfunction "TMS_14") (pintype "input"))
      (node (ref "J13") (pin "5") (pinfunction "5_5") (pintype "bidirectional"))
    )
    (net (code "61") (name "/TRG") (class "Default")
      (node (ref "J4") (pin "7") (pinfunction "7_7") (pintype "bidirectional"))
      (node (ref "J9") (pin "7") (pinfunction "7_7") (pintype "bidirectional"))
    )
    (net (code "62") (name "GND") (class "Default")
      (node (ref "C11") (pin "1") (pinfunction "1_1") (pintype "passive"))
      (node (ref "C18") (pin "1") (pinfunction "1_1") (pintype "passive"))
      (node (ref "C19") (pin "1") (pinfunction "1_1") (pintype "passive"))
      (node (ref "C2") (pin "1") (pinfunction "1_1") (pintype "passive"))
      (node (ref "C20") (pin "1") (pinfunction "1_1") (pintype "passive"))
      (node (ref "C21") (pin "1") (pinfunction "1_1") (pintype "passive"))
      (node (ref "C231") (pin "1") (pinfunction "1_1") (pintype "passive"))
      (node (ref "C232") (pin "1") (pinfunction "1_1") (pintype "passive"))
      (node (ref "C25") (pin "1") (pinfunction "1_1") (pintype "passive"))
      (node (ref "C26") (pin "1") (pinfunction "1_1") (pintype "passive"))
      (node (ref "C3") (pin "1") (pinfunction "1_1") (pintype "passive"))
      (node (ref "C4") (pin "1") (pinfunction "1_1") (pintype "passive"))
      (node (ref "C61") (pin "1") (pinfunction "1_1") (pintype "passive"))
      (node (ref "IC2") (pin "2") (pinfunction "GND_2") (pintype "power_in"))
      (node (ref "IC3") (pin "65") (pinfunction "GND_65") (pintype "power_in"))
      (node (ref "IC4") (pin "2") (pinfunction "GND_2") (pintype "power_in"))
      (node (ref "IC7") (pin "2") (pinfunction "GND_2") (pintype "power_in"))
      (node (ref "J10") (pin "11") (pinfunction "11_11") (pintype "bidirectional"))
      (node (ref "J10") (pin "7") (pinfunction "7_7") (pintype "bidirectional"))
      (node (ref "J100") (pin "9") (pinfunction "9_9") (pintype "bidirectional"))
      (node (ref "J11") (pin "11") (pinfunction "11_11") (pintype "bidirectional"))
      (node (ref "J11") (pin "7") (pinfunction "7_7") (pintype "bidirectional"))
      (node (ref "J11L") (pin "2") (pinfunction "2_2") (pintype "bidirectional"))
      (node (ref "J11L") (pin "9") (pinfunction "9_9") (pintype "bidirectional"))
      (node (ref "J12") (pin "9") (pinfunction "9_9") (pintype "bidirectional"))
      (node (ref "J13") (pin "10") (pinfunction "10_10") (pintype "bidirectional"))
      (node (ref "J13") (pin "2") (pinfunction "2_2") (pintype "bidirectional"))
      (node (ref "J4") (pin "1") (pinfunction "1_1") (pintype "bidirectional"))
      (node (ref "J4") (pin "5") (pinfunction "5_5") (pintype "bidirectional"))
      (node (ref "J4") (pin "9") (pinfunction "9_9") (pintype "bidirectional"))
      (node (ref "J9") (pin "1") (pinfunction "1_1") (pintype "bidirectional"))
      (node (ref "J9") (pin "5") (pinfunction "5_5") (pintype "bidirectional"))
      (node (ref "J9") (pin "9") (pinfunction "9_9") (pintype "bidirectional"))
      (node (ref "J9R") (pin "2") (pinfunction "2_2") (pintype "bidirectional"))
      (node (ref "J9R") (pin "9") (pinfunction "9_9") (pintype "bidirectional"))
      (node (ref "LD1") (pin "1") (pinfunction "C_1") (pintype "passive"))
      (node (ref "MP1") (pin "1") (pinfunction "1_1") (pintype "passive"))
      (node (ref "MP2") (pin "1") (pinfunction "1_1") (pintype "passive"))
      (node (ref "MP3") (pin "1") (pinfunction "1_1") (pintype "passive"))
      (node (ref "MP4") (pin "1") (pinfunction "1_1") (pintype "passive"))
      (node (ref "NT1") (pin "2") (pinfunction "2_2") (pintype "bidirectional"))
      (node (ref "NT10") (pin "2") (pinfunction "2_2") (pintype "bidirectional"))
      (node (ref "NT11") (pin "2") (pinfunction "2_2") (pintype "bidirectional"))
      (node (ref "NT12") (pin "2") (pinfunction "2_2") (pintype "bidirectional"))
      (node (ref "NT13") (pin "2") (pinfunction "2_2") (pintype "bidirectional"))
      (node (ref "NT2") (pin "2") (pinfunction "2_2") (pintype "bidirectional"))
      (node (ref "NT3") (pin "2") (pinfunction "2_2") (pintype "bidirectional"))
      (node (ref "NT4") (pin "2") (pinfunction "2_2") (pintype "bidirectional"))
      (node (ref "NT5") (pin "2") (pinfunction "2_2") (pintype "bidirectional"))
      (node (ref "NT6") (pin "2") (pinfunction "2_2") (pintype "bidirectional"))
      (node (ref "NT7") (pin "2") (pinfunction "2_2") (pintype "bidirectional"))
      (node (ref "NT9") (pin "2") (pinfunction "2_2") (pintype "bidirectional"))
      (node (ref "SW2") (pin "5") (pinfunction "5_5") (pintype "bidirectional"))
      (node (ref "SW2") (pin "6") (pinfunction "6_6") (pintype "bidirectional"))
      (node (ref "SW2") (pin "7") (pinfunction "7_7") (pintype "bidirectional"))
      (node (ref "SW2") (pin "8") (pinfunction "8_8") (pintype "bidirectional"))
    )
    (net (code "63") (name "Net-(LD1-A)") (class "Default")
      (node (ref "LD1") (pin "2") (pinfunction "A_2") (pintype "passive"))
      (node (ref "R34") (pin "1") (pinfunction "1_1") (pintype "passive"))
    )
    (net (code "64") (name "Net-(LD18-C)") (class "Default")
      (node (ref "LD18") (pin "1") (pinfunction "C_1") (pintype "passive"))
      (node (ref "R26") (pin "1") (pinfunction "1_1") (pintype "passive"))
    )
    (net (code "65") (name "Net-(LD19-C)") (class "Default")
      (node (ref "LD19") (pin "1") (pinfunction "C_1") (pintype "passive"))
      (node (ref "R27") (pin "1") (pinfunction "1_1") (pintype "passive"))
    )
    (net (code "66") (name "Net-(LD20-C)") (class "Default")
      (node (ref "LD20") (pin "1") (pinfunction "C_1") (pintype "passive"))
      (node (ref "R32") (pin "1") (pinfunction "1_1") (pintype "passive"))
    )
    (net (code "67") (name "Net-(LD21-C)") (class "Default")
      (node (ref "LD21") (pin "1") (pinfunction "C_1") (pintype "passive"))
      (node (ref "R33") (pin "1") (pinfunction "1_1") (pintype "passive"))
    )
    (net (code "68") (name "P1V8") (class "Default")
      (node (ref "C21") (pin "2") (pinfunction "2_2") (pintype "passive"))
      (node (ref "C232") (pin "2") (pinfunction "2_2") (pintype "passive"))
      (node (ref "C61") (pin "2") (pinfunction "2_2") (pintype "passive"))
      (node (ref "IC3") (pin "41") (pinfunction "VCCINT_41") (pintype "power_in"))
      (node (ref "IC3") (pin "8") (pinfunction "VCCINT_8") (pintype "power_in"))
      (node (ref "IC4") (pin "5") (pinfunction "VOUT_5") (pintype "power_in"))
    )
    (net (code "69") (name "P3V3") (class "Default")
      (node (ref "C11") (pin "2") (pinfunction "2_2") (pintype "passive"))
      (node (ref "C19") (pin "2") (pinfunction "2_2") (pintype "passive"))
      (node (ref "C2") (pin "2") (pinfunction "2_2") (pintype "passive"))
      (node (ref "C3") (pin "2") (pinfunction "2_2") (pintype "passive"))
      (node (ref "C4") (pin "2") (pinfunction "2_2") (pintype "passive"))
      (node (ref "D5") (pin "1") (pinfunction "C_1") (pintype "passive"))
      (node (ref "IC3") (pin "23") (pinfunction "VCCIO1_23") (pintype "power_in"))
      (node (ref "IC3") (pin "39") (pinfunction "VCCIO2_39") (pintype "power_in"))
      (node (ref "IC3") (pin "57") (pinfunction "VCCIO2_57") (pintype "power_in"))
      (node (ref "IC3") (pin "6") (pinfunction "VCCIO1_6") (pintype "power_in"))
      (node (ref "IC7") (pin "5") (pinfunction "VOUT_5") (pintype "power_in"))
      (node (ref "J13") (pin "4") (pinfunction "4_4") (pintype "bidirectional"))
      (node (ref "LD18") (pin "2") (pinfunction "A_2") (pintype "passive"))
      (node (ref "LD19") (pin "2") (pinfunction "A_2") (pintype "passive"))
      (node (ref "LD20") (pin "2") (pinfunction "A_2") (pintype "passive"))
      (node (ref "LD21") (pin "2") (pinfunction "A_2") (pintype "passive"))
    )
    (net (code "70") (name "P3V3_TDC") (class "Default")
      (node (ref "C26") (pin "2") (pinfunction "2_2") (pintype "passive"))
      (node (ref "IC2") (pin "5") (pinfunction "VOUT_5") (pintype "power_in"))
    )
    (net (code "71") (name "P5V0") (class "Default")
      (node (ref "C20") (pin "2") (pinfunction "2_2") (pintype "passive"))
      (node (ref "C231") (pin "2") (pinfunction "2_2") (pintype "passive"))
      (node (ref "C25") (pin "2") (pinfunction "2_2") (pintype "passive"))
      (node (ref "IC2") (pin "1") (pinfunction "VIN_1") (pintype "input"))
      (node (ref "IC2") (pin "3") (pinfunction "EN_3") (pintype "input"))
      (node (ref "IC4") (pin "1") (pinfunction "VIN_1") (pintype "input"))
      (node (ref "IC4") (pin "3") (pinfunction "EN_3") (pintype "input"))
      (node (ref "IC7") (pin "1") (pinfunction "VIN_1") (pintype "input"))
      (node (ref "IC7") (pin "3") (pinfunction "EN_3") (pintype "input"))
      (node (ref "J10") (pin "2") (pinfunction "2_2") (pintype "bidirectional"))
      (node (ref "J100") (pin "1") (pinfunction "1_1") (pintype "bidirectional"))
      (node (ref "J11") (pin "2") (pinfunction "2_2") (pintype "bidirectional"))
      (node (ref "J12") (pin "1") (pinfunction "1_1") (pintype "bidirectional"))
    )
    (net (code "72") (name "P12V0") (class "Default")
      (node (ref "J10") (pin "1") (pinfunction "1_1") (pintype "bidirectional"))
      (node (ref "J10") (pin "3") (pinfunction "3_3") (pintype "bidirectional"))
      (node (ref "J100") (pin "2") (pinfunction "2_2") (pintype "bidirectional"))
      (node (ref "J11") (pin "1") (pinfunction "1_1") (pintype "bidirectional"))
      (node (ref "J11") (pin "3") (pinfunction "3_3") (pintype "bidirectional"))
      (node (ref "J12") (pin "2") (pinfunction "2_2") (pintype "bidirectional"))
    )
    (net (code "73") (name "unconnected-(IC2-NC-Pad4)") (class "Default")
      (node (ref "IC2") (pin "4") (pinfunction "NC_4") (pintype "passive"))
    )
    (net (code "74") (name "unconnected-(IC4-NC-Pad4)") (class "Default")
      (node (ref "IC4") (pin "4") (pinfunction "NC_4") (pintype "passive"))
    )
    (net (code "75") (name "unconnected-(IC7-NC-Pad4)") (class "Default")
      (node (ref "IC7") (pin "4") (pinfunction "NC_4") (pintype "passive"))
    )
    (net (code "76") (name "unconnected-(J13-Pad6)") (class "Default")
      (node (ref "J13") (pin "6") (pinfunction "6_6") (pintype "bidirectional"))
    )
    (net (code "77") (name "unconnected-(J13-Pad7)") (class "Default")
      (node (ref "J13") (pin "7") (pinfunction "7_7") (pintype "bidirectional"))
    )
    (net (code "78") (name "unconnected-(J13-Pad8)") (class "Default")
      (node (ref "J13") (pin "8") (pinfunction "8_8") (pintype "bidirectional"))
    )
  )
)
